# 2_Controller_A20_ESP32.net
KiCad netlist of a schematic drawn in Altium Designer
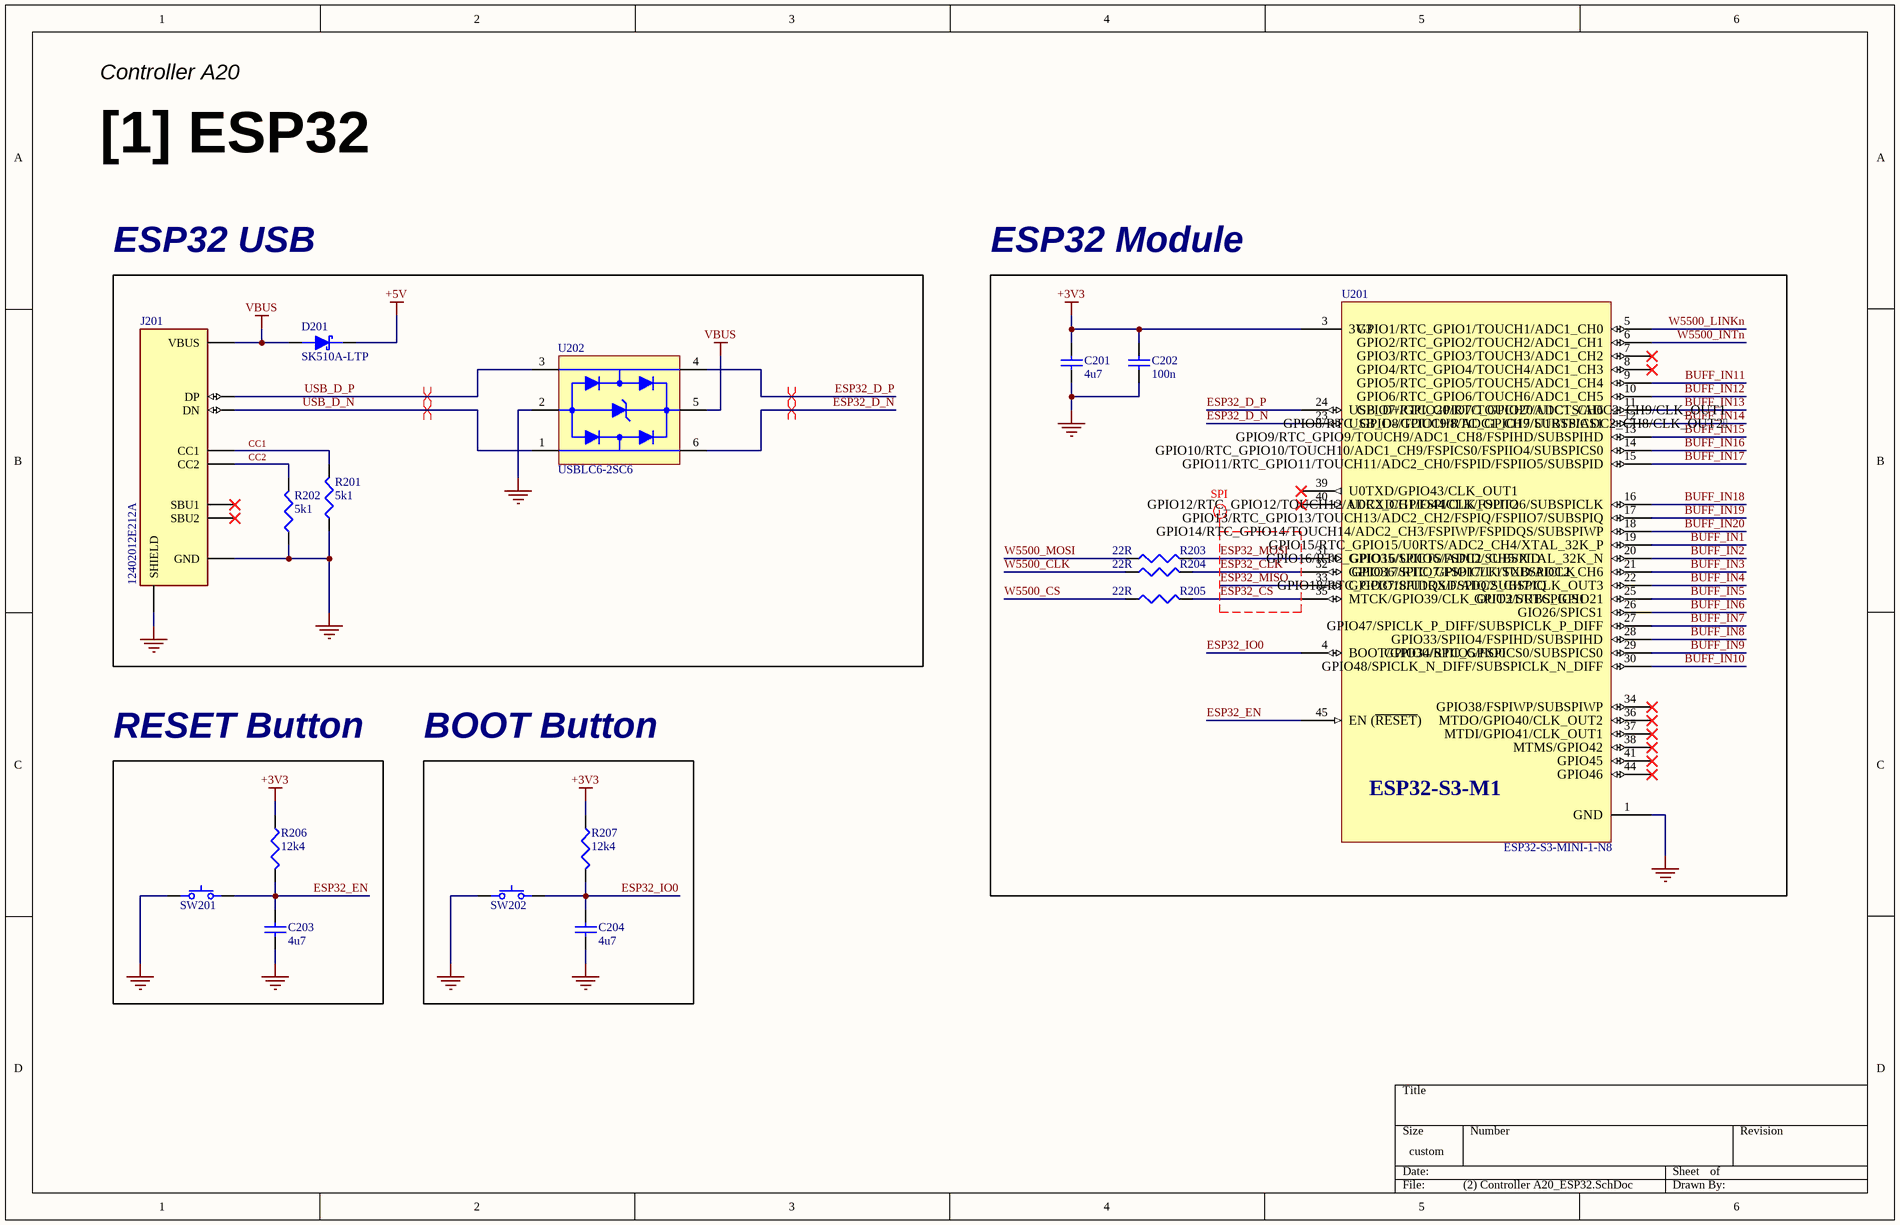
[diagram p0: (2) Controller A20_ESP32.SchDoc]

(export (version "E")
  (design (tool "Eeschema 10.0.6"))
  (components
    (comp (ref "C201")
      (value "4u7")
      (footprint "C0805")
      (description "4.7 µF ±20% 50V Ceramic Capacitor X7R 0805 (2012 Metric)")
      (fields
        (field (name "MANUFACTURER") "Murata Electronics")
        (field (name "MFR. PART #") "GRM21BZ71H475ME15K")
      )
      (libsource (lib "Symbols") (part "CAP 4.7uF 50V"))
    )
    (comp (ref "C202")
      (value "100n")
      (footprint "C0603")
      (description "0.1 µF ±10% 50V Ceramic Capacitor X7R 0603 (1608 Metric)")
      (fields (field (name "MANUFACTURER") "KEMET") (field (name "MFR. PART #") "C0603C104K5RACTU"))
      (libsource (lib "Symbols") (part "CAP 100nF 50V"))
    )
    (comp (ref "C203")
      (value "4u7")
      (footprint "C0805")
      (description "4.7 µF ±20% 50V Ceramic Capacitor X7R 0805 (2012 Metric)")
      (fields
        (field (name "MANUFACTURER") "Murata Electronics")
        (field (name "MFR. PART #") "GRM21BZ71H475ME15K")
      )
      (libsource (lib "Symbols") (part "CAP 4.7uF 50V"))
    )
    (comp (ref "C204")
      (value "4u7")
      (footprint "C0805")
      (description "4.7 µF ±20% 50V Ceramic Capacitor X7R 0805 (2012 Metric)")
      (fields
        (field (name "MANUFACTURER") "Murata Electronics")
        (field (name "MFR. PART #") "GRM21BZ71H475ME15K")
      )
      (libsource (lib "Symbols") (part "CAP 4.7uF 50V"))
    )
    (comp (ref "D201")
      (value "SK510A-LTP")
      (footprint "DO-214AC(SMA)")
      (description "Diode 100 V 5A Surface Mount DO-214AC (SMA)")
      (fields (field (name "MANUFACTURER") "MCC (Micro Commercial Components)"))
      (libsource (lib "Symbols") (part "SK510A-LTP 100V 5A Schottky Diode"))
    )
    (comp (ref "J201")
      (value "12402012E212A")
      (footprint "USB-C Female 16P")
      (fields (field (name "MANUFACTURER") "Amphenol ICC (Commercial Products)"))
      (libsource (lib "Symbols") (part "USB2.0 Type-C Connector"))
    )
    (comp (ref "R201")
      (value "5k1")
      (footprint "R0603")
      (description "5.1 kOhms ±1% 0.1W, 1/10W Chip Resistor 0603 (1608 Metric) Moisture Resistant Thick Film")
      (fields (field (name "MANUFACTURER") "YAGEO") (field (name "MFR. PART #") "RC0603FR-075K1L"))
      (libsource (lib "Symbols") (part "RES 5.1k"))
    )
    (comp (ref "R202")
      (value "5k1")
      (footprint "R0603")
      (description "5.1 kOhms ±1% 0.1W, 1/10W Chip Resistor 0603 (1608 Metric) Moisture Resistant Thick Film")
      (fields (field (name "MANUFACTURER") "YAGEO") (field (name "MFR. PART #") "RC0603FR-075K1L"))
      (libsource (lib "Symbols") (part "RES 5.1k"))
    )
    (comp (ref "R203")
      (value "22R")
      (footprint "R0402")
      (description "22 Ohms ±1% 0.063W, 1/16W Chip Resistor 0402 (1005 Metric) Moisture Resistant Thick Film")
      (fields (field (name "MANUFACTURER") "YAGEO") (field (name "MFR. PART #") "RC0402FR-0722RL"))
      (libsource (lib "Symbols") (part "RES 22R"))
    )
    (comp (ref "R204")
      (value "22R")
      (footprint "R0402")
      (description "22 Ohms ±1% 0.063W, 1/16W Chip Resistor 0402 (1005 Metric) Moisture Resistant Thick Film")
      (fields (field (name "MANUFACTURER") "YAGEO") (field (name "MFR. PART #") "RC0402FR-0722RL"))
      (libsource (lib "Symbols") (part "RES 22R"))
    )
    (comp (ref "R205")
      (value "22R")
      (footprint "R0402")
      (description "22 Ohms ±1% 0.063W, 1/16W Chip Resistor 0402 (1005 Metric) Moisture Resistant Thick Film")
      (fields (field (name "MANUFACTURER") "YAGEO") (field (name "MFR. PART #") "RC0402FR-0722RL"))
      (libsource (lib "Symbols") (part "RES 22R"))
    )
    (comp (ref "R206")
      (value "12k4")
      (footprint "R0603")
      (description "12.4 kOhms ±1% 0.1W, 1/10W Chip Resistor 0603 (1608 Metric) Moisture Resistant Thick Film")
      (fields (field (name "MANUFACTURER") "YAGEO") (field (name "MFR. PART #") "RC0603FR-0712K4L"))
      (libsource (lib "Symbols") (part "RES 12.4k"))
    )
    (comp (ref "R207")
      (value "12k4")
      (footprint "R0603")
      (description "12.4 kOhms ±1% 0.1W, 1/10W Chip Resistor 0603 (1608 Metric) Moisture Resistant Thick Film")
      (fields (field (name "MANUFACTURER") "YAGEO") (field (name "MFR. PART #") "RC0603FR-0712K4L"))
      (libsource (lib "Symbols") (part "RES 12.4k"))
    )
    (comp (ref "SW201")
      (value "SKRPANE010")
      (footprint "SMD Tactile Switch")
      (fields (field (name "MANUFACTURER") "ALPSALPINE"))
      (libsource (lib "Symbols") (part "Tactile Switch"))
    )
    (comp (ref "SW202")
      (value "SKRPANE010")
      (footprint "SMD Tactile Switch")
      (fields (field (name "MANUFACTURER") "ALPSALPINE"))
      (libsource (lib "Symbols") (part "Tactile Switch"))
    )
    (comp (ref "U201")
      (value "ESP32-S3-MINI-1-N8")
      (footprint "ESP32-S3-MINI-1-N8")
      (fields (field (name "MANUFACTURER") "Espressif Systems"))
      (libsource (lib "Symbols") (part "ESP32-S3-MINI-1-N8"))
    )
    (comp (ref "U202")
      (value "USBLC6-2SC6")
      (footprint "SOT23-6L")
      (description "17V Clamp 5A (8/20µs) Ipp Tvs Diode Surface Mount SOT-23-6")
      (fields (field (name "MANUFACTURER") "STMicroelectronics"))
      (libsource (lib "Symbols") (part "USBLC6-2SC6 ESD Array 5.25VRWM"))
    )
  )
  (nets
    (net (code "1") (name "+3V3") (class "Default")
      (node (ref "C201") (pin "2") (pinfunction "2_2") (pintype "passive"))
      (node (ref "C202") (pin "2") (pinfunction "2_2") (pintype "passive"))
      (node (ref "R206") (pin "2") (pinfunction "2_2") (pintype "passive"))
      (node (ref "R207") (pin "2") (pinfunction "2_2") (pintype "passive"))
      (node (ref "U201") (pin "3") (pinfunction "3V3_3") (pintype "power_in"))
    )
    (net (code "2") (name "+5V") (class "Default")
      (node (ref "D201") (pin "2") (pinfunction "2_2") (pintype "passive"))
    )
    (net (code "3") (name "/BUFF_IN1") (class "Default")
      (node (ref "U201") (pin "19") (pinfunction "GPIO15/RTC_GPIO15/U0RTS/ADC2_CH4/XTAL_32K_P_19") (pintype "bidirectional"))
    )
    (net (code "4") (name "/BUFF_IN2") (class "Default")
      (node (ref "U201") (pin "20") (pinfunction "GPIO16/RTC_GPIO16/U0CTS/ADC2_CH5/XTAL_32K_N_20") (pintype "bidirectional"))
    )
    (net (code "5") (name "/BUFF_IN3") (class "Default")
      (node (ref "U201") (pin "21") (pinfunction "GPIO17/RTC_GPIO17/U1TXD/ADC2_CH6_21") (pintype "bidirectional"))
    )
    (net (code "6") (name "/BUFF_IN4") (class "Default")
      (node (ref "U201") (pin "22") (pinfunction "GPIO18/RTC_GPIO18/U1RXD/ADC2_CH7/CLK_OUT3_22") (pintype "bidirectional"))
    )
    (net (code "7") (name "/BUFF_IN5") (class "Default")
      (node (ref "U201") (pin "25") (pinfunction "GPIO21/RTC_GPIO21_25") (pintype "bidirectional"))
    )
    (net (code "8") (name "/BUFF_IN6") (class "Default")
      (node (ref "U201") (pin "26") (pinfunction "GIO26/SPICS1_26") (pintype "bidirectional"))
    )
    (net (code "9") (name "/BUFF_IN7") (class "Default")
      (node (ref "U201") (pin "27") (pinfunction "GPIO47/SPICLK_P_DIFF/SUBSPICLK_P_DIFF_27") (pintype "bidirectional"))
    )
    (net (code "10") (name "/BUFF_IN8") (class "Default")
      (node (ref "U201") (pin "28") (pinfunction "GPIO33/SPIIO4/FSPIHD/SUBSPIHD_28") (pintype "bidirectional"))
    )
    (net (code "11") (name "/BUFF_IN9") (class "Default")
      (node (ref "U201") (pin "29") (pinfunction "GPIO34/SPIIO5/FSPICS0/SUBSPICS0_29") (pintype "bidirectional"))
    )
    (net (code "12") (name "/BUFF_IN10") (class "Default")
      (node (ref "U201") (pin "30") (pinfunction "GPIO48/SPICLK_N_DIFF/SUBSPICLK_N_DIFF_30") (pintype "bidirectional"))
    )
    (net (code "13") (name "/BUFF_IN11") (class "Default")
      (node (ref "U201") (pin "9") (pinfunction "GPIO5/RTC_GPIO5/TOUCH5/ADC1_CH4_9") (pintype "bidirectional"))
    )
    (net (code "14") (name "/BUFF_IN12") (class "Default")
      (node (ref "U201") (pin "10") (pinfunction "GPIO6/RTC_GPIO6/TOUCH6/ADC1_CH5_10") (pintype "bidirectional"))
    )
    (net (code "15") (name "/BUFF_IN13") (class "Default")
      (node (ref "U201") (pin "11") (pinfunction "GPIO7/RTC_GPIO7/TOUCH7/ADC1_CH6_11") (pintype "bidirectional"))
    )
    (net (code "16") (name "/BUFF_IN14") (class "Default")
      (node (ref "U201") (pin "12") (pinfunction "GPIO8/RTC_GPIO8/TOUCH8/ADC1_CH7/SUBSPICS1_12") (pintype "bidirectional"))
    )
    (net (code "17") (name "/BUFF_IN15") (class "Default")
      (node (ref "U201") (pin "13") (pinfunction "GPIO9/RTC_GPIO9/TOUCH9/ADC1_CH8/FSPIHD/SUBSPIHD_13") (pintype "bidirectional"))
    )
    (net (code "18") (name "/BUFF_IN16") (class "Default")
      (node (ref "U201") (pin "14") (pinfunction "GPIO10/RTC_GPIO10/TOUCH10/ADC1_CH9/FSPICS0/FSPIIO4/SUBSPICS0_14") (pintype "bidirectional"))
    )
    (net (code "19") (name "/BUFF_IN17") (class "Default")
      (node (ref "U201") (pin "15") (pinfunction "GPIO11/RTC_GPIO11/TOUCH11/ADC2_CH0/FSPID/FSPIIO5/SUBSPID_15") (pintype "bidirectional"))
    )
    (net (code "20") (name "/BUFF_IN18") (class "Default")
      (node (ref "U201") (pin "16") (pinfunction "GPIO12/RTC_GPIO12/TOUCH12/ADC2_CH1/FSPICLK/FSPIIO6/SUBSPICLK_16") (pintype "bidirectional"))
    )
    (net (code "21") (name "/BUFF_IN19") (class "Default")
      (node (ref "U201") (pin "17") (pinfunction "GPIO13/RTC_GPIO13/TOUCH13/ADC2_CH2/FSPIQ/FSPIIO7/SUBSPIQ_17") (pintype "bidirectional"))
    )
    (net (code "22") (name "/BUFF_IN20") (class "Default")
      (node (ref "U201") (pin "18") (pinfunction "GPIO14/RTC_GPIO14/TOUCH14/ADC2_CH3/FSPIWP/FSPIDQS/SUBSPIWP_18") (pintype "bidirectional"))
    )
    (net (code "23") (name "/CC1") (class "Default")
      (node (ref "J201") (pin "A5") (pinfunction "CC1_A5") (pintype "passive"))
      (node (ref "R201") (pin "2") (pinfunction "2_2") (pintype "passive"))
    )
    (net (code "24") (name "/CC2") (class "Default")
      (node (ref "J201") (pin "B5") (pinfunction "CC2_B5") (pintype "passive"))
      (node (ref "R202") (pin "2") (pinfunction "2_2") (pintype "passive"))
    )
    (net (code "25") (name "/ESP32_CLK") (class "Default")
      (node (ref "R204") (pin "2") (pinfunction "2_2") (pintype "passive"))
      (node (ref "U201") (pin "32") (pinfunction "GPIO36/SPIIO7/FSPICLK/SUBSPICLK_32") (pintype "bidirectional"))
    )
    (net (code "26") (name "/ESP32_CS") (class "Default")
      (node (ref "R205") (pin "2") (pinfunction "2_2") (pintype "passive"))
      (node (ref "U201") (pin "35") (pinfunction "MTCK/GPIO39/CLK_OUT3/SUBSPICS1_35") (pintype "bidirectional"))
    )
    (net (code "27") (name "/ESP32_D_N") (class "Default")
      (node (ref "U201") (pin "23") (pinfunction "USB_D-/GPIO19/RTC_GPIO19/U1RTS/ADC2_CH8/CLK_OUT2_23") (pintype "bidirectional"))
      (node (ref "U202") (pin "6") (pinfunction "6_6") (pintype "passive"))
    )
    (net (code "28") (name "/ESP32_D_P") (class "Default")
      (node (ref "U201") (pin "24") (pinfunction "USB_D+/GPIO20/RTC_GPIO20/U1CTS/ADC2_CH9/CLK_OUT1_24") (pintype "bidirectional"))
      (node (ref "U202") (pin "4") (pinfunction "4_4") (pintype "passive"))
    )
    (net (code "29") (name "/ESP32_EN") (class "Default")
      (node (ref "C203") (pin "2") (pinfunction "2_2") (pintype "passive"))
      (node (ref "R206") (pin "1") (pinfunction "1_1") (pintype "passive"))
      (node (ref "SW201") (pin "1") (pinfunction "1_1") (pintype "passive"))
      (node (ref "U201") (pin "45") (pinfunction "EN_(~{RESET})_45") (pintype "input"))
    )
    (net (code "30") (name "/ESP32_IO0") (class "Default")
      (node (ref "C204") (pin "2") (pinfunction "2_2") (pintype "passive"))
      (node (ref "R207") (pin "1") (pinfunction "1_1") (pintype "passive"))
      (node (ref "SW202") (pin "1") (pinfunction "1_1") (pintype "passive"))
      (node (ref "U201") (pin "4") (pinfunction "BOOT/GPIO0/RTC_GPIO0_4") (pintype "bidirectional"))
    )
    (net (code "31") (name "/ESP32_MISO") (class "Default")
      (node (ref "U201") (pin "33") (pinfunction "GPIO37/SPIDQS/FSPIQ/SUBSPIQ_33") (pintype "bidirectional"))
    )
    (net (code "32") (name "/ESP32_MOSI") (class "Default")
      (node (ref "R203") (pin "2") (pinfunction "2_2") (pintype "passive"))
      (node (ref "U201") (pin "31") (pinfunction "GPIO35/SPIIO6/FSPID/SUBSPID_31") (pintype "bidirectional"))
    )
    (net (code "33") (name "/USB_D_N") (class "Default")
      (node (ref "J201") (pin "A7/B7") (pinfunction "DN_A7/B7") (pintype "bidirectional"))
      (node (ref "U202") (pin "1") (pinfunction "1_1") (pintype "passive"))
    )
    (net (code "34") (name "/USB_D_P") (class "Default")
      (node (ref "J201") (pin "A6/B6") (pinfunction "DP_A6/B6") (pintype "bidirectional"))
      (node (ref "U202") (pin "3") (pinfunction "3_3") (pintype "passive"))
    )
    (net (code "35") (name "/W5500_CLK") (class "Default")
      (node (ref "R204") (pin "1") (pinfunction "1_1") (pintype "passive"))
    )
    (net (code "36") (name "/W5500_CS") (class "Default")
      (node (ref "R205") (pin "1") (pinfunction "1_1") (pintype "passive"))
    )
    (net (code "37") (name "/W5500_INTn") (class "Default")
      (node (ref "U201") (pin "6") (pinfunction "GPIO2/RTC_GPIO2/TOUCH2/ADC1_CH1_6") (pintype "bidirectional"))
    )
    (net (code "38") (name "/W5500_LINKn") (class "Default")
      (node (ref "U201") (pin "5") (pinfunction "GPIO1/RTC_GPIO1/TOUCH1/ADC1_CH0_5") (pintype "bidirectional"))
    )
    (net (code "39") (name "/W5500_MOSI") (class "Default")
      (node (ref "R203") (pin "1") (pinfunction "1_1") (pintype "passive"))
    )
    (net (code "40") (name "GND") (class "Default")
      (node (ref "C201") (pin "1") (pinfunction "1_1") (pintype "passive"))
      (node (ref "C202") (pin "1") (pinfunction "1_1") (pintype "passive"))
      (node (ref "C203") (pin "1") (pinfunction "1_1") (pintype "passive"))
      (node (ref "C204") (pin "1") (pinfunction "1_1") (pintype "passive"))
      (node (ref "J201") (pin "A1B12/B1A12") (pinfunction "GND_A1B12/B1A12") (pintype "power_in"))
      (node (ref "J201") (pin "SH") (pinfunction "SHIELD_SH") (pintype "power_in"))
      (node (ref "R201") (pin "1") (pinfunction "1_1") (pintype "passive"))
      (node (ref "R202") (pin "1") (pinfunction "1_1") (pintype "passive"))
      (node (ref "SW201") (pin "2") (pinfunction "2_2") (pintype "passive"))
      (node (ref "SW202") (pin "2") (pinfunction "2_2") (pintype "passive"))
      (node (ref "U201") (pin "1") (pinfunction "GND_1") (pintype "power_in"))
      (node (ref "U202") (pin "2") (pinfunction "2_2") (pintype "passive"))
    )
    (net (code "41") (name "VBUS") (class "Default")
      (node (ref "D201") (pin "1") (pinfunction "1_1") (pintype "passive"))
      (node (ref "J201") (pin "A4B9/_B4A9") (pinfunction "VBUS_A4B9/_B4A9") (pintype "power_in"))
      (node (ref "U202") (pin "5") (pinfunction "5_5") (pintype "passive"))
    )
    (net (code "42") (name "unconnected-(J201-SBU1-PadA8)") (class "Default")
      (node (ref "J201") (pin "A8") (pinfunction "SBU1_A8") (pintype "passive+no_connect"))
    )
    (net (code "43") (name "unconnected-(J201-SBU2-PadB8)") (class "Default")
      (node (ref "J201") (pin "B8") (pinfunction "SBU2_B8") (pintype "passive+no_connect"))
    )
    (net (code "44") (name "unconnected-(U201-GPIO3{slash}RTC_GPIO3{slash}TOUCH3{slash}ADC1_CH2-Pad7)") (class "Default")
      (node (ref "U201") (pin "7") (pinfunction "GPIO3/RTC_GPIO3/TOUCH3/ADC1_CH2_7") (pintype "bidirectional+no_connect"))
    )
    (net (code "45") (name "unconnected-(U201-GPIO4{slash}RTC_GPIO4{slash}TOUCH4{slash}ADC1_CH3-Pad8)") (class "Default")
      (node (ref "U201") (pin "8") (pinfunction "GPIO4/RTC_GPIO4/TOUCH4/ADC1_CH3_8") (pintype "bidirectional+no_connect"))
    )
    (net (code "46") (name "unconnected-(U201-GPIO38{slash}FSPIWP{slash}SUBSPIWP-Pad34)") (class "Default")
      (node (ref "U201") (pin "34") (pinfunction "GPIO38/FSPIWP/SUBSPIWP_34") (pintype "bidirectional+no_connect"))
    )
    (net (code "47") (name "unconnected-(U201-GPIO45-Pad41)") (class "Default")
      (node (ref "U201") (pin "41") (pinfunction "GPIO45_41") (pintype "bidirectional+no_connect"))
    )
    (net (code "48") (name "unconnected-(U201-GPIO46-Pad44)") (class "Default")
      (node (ref "U201") (pin "44") (pinfunction "GPIO46_44") (pintype "bidirectional+no_connect"))
    )
    (net (code "49") (name "unconnected-(U201-MTDI{slash}GPIO41{slash}CLK_OUT1-Pad37)") (class "Default")
      (node (ref "U201") (pin "37") (pinfunction "MTDI/GPIO41/CLK_OUT1_37") (pintype "bidirectional+no_connect"))
    )
    (net (code "50") (name "unconnected-(U201-MTDO{slash}GPIO40{slash}CLK_OUT2-Pad36)") (class "Default")
      (node (ref "U201") (pin "36") (pinfunction "MTDO/GPIO40/CLK_OUT2_36") (pintype "bidirectional+no_connect"))
    )
    (net (code "51") (name "unconnected-(U201-MTMS{slash}GPIO42-Pad38)") (class "Default")
      (node (ref "U201") (pin "38") (pinfunction "MTMS/GPIO42_38") (pintype "bidirectional+no_connect"))
    )
    (net (code "52") (name "unconnected-(U201-U0RXD{slash}GPIO44{slash}CLK_OUT2-Pad40)") (class "Default")
      (node (ref "U201") (pin "40") (pinfunction "U0RXD/GPIO44/CLK_OUT2_40") (pintype "input+no_connect"))
    )
    (net (code "53") (name "unconnected-(U201-U0TXD{slash}GPIO43{slash}CLK_OUT1-Pad39)") (class "Default")
      (node (ref "U201") (pin "39") (pinfunction "U0TXD/GPIO43/CLK_OUT1_39") (pintype "output+no_connect"))
    )
  )
)
